# Sheet1.net
KiCad netlist of a schematic drawn in Altium Designer
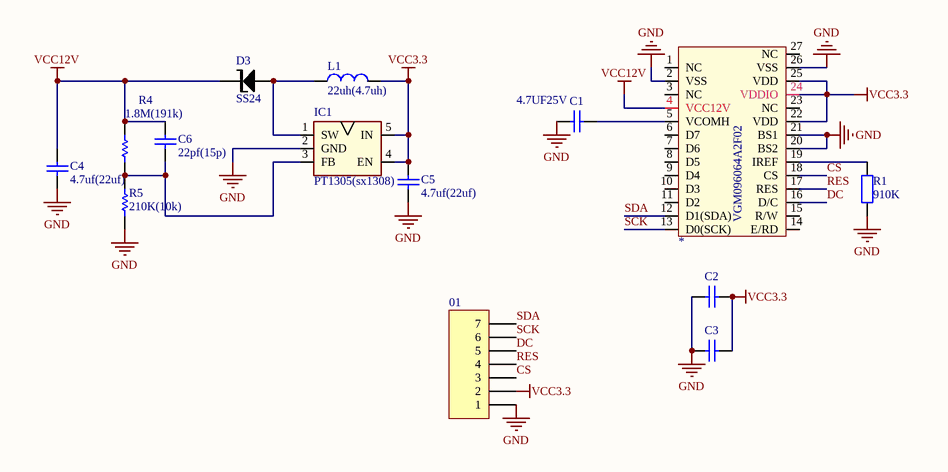
[diagram p0: Sheet1.SchDoc]

(export (version "E")
  (design (tool "Eeschema 10.0.6"))
  (components
    (comp (ref "*")
      (value "VGM096064A2F02")
      (footprint "VGM096064A2F02")
      (libsource (lib "COG-C177MVHG-03(pin23_08)") (part "VGM096064A2F02"))
    )
    (comp (ref "01")
      (value "Header 7")
      (footprint "HDR1X7")
      (description "Header, 7-Pin")
      (fields (field (name "PUBLISHER") "Altium Limited"))
      (libsource (lib "Miscellaneous Connectors") (part "Header 7"))
    )
    (comp (ref "C1")
      (value "4.7UF25V")
      (footprint "LC-0805_C")
      (description "Capacitor")
      (fields (field (name "Comment") "Cap") (field (name "PUBLISHER") "Altium Limited"))
      (libsource (lib "Miscellaneous Devices") (part "Cap"))
    )
    (comp (ref "C2")
      (value "Cap")
      (footprint "LC-0805_C")
      (description "Capacitor")
      (fields (field (name "PUBLISHER") "Altium Limited"))
      (libsource (lib "Miscellaneous Devices") (part "Cap"))
    )
    (comp (ref "C3")
      (value "Cap")
      (footprint "LC-0805_C")
      (description "Capacitor")
      (fields (field (name "PUBLISHER") "Altium Limited"))
      (libsource (lib "Miscellaneous Devices") (part "Cap"))
    )
    (comp (ref "C4")
      (value "4.7uf(22uf)")
      (footprint "LC-0805_C")
      (description "Capacitor")
      (fields (field (name "Comment") "Cap") (field (name "PUBLISHER") "Altium Limited"))
      (libsource (lib "Miscellaneous Devices") (part "Cap"))
    )
    (comp (ref "C5")
      (value "4.7uf(22uf)")
      (footprint "LC-0805_C")
      (description "Capacitor")
      (fields (field (name "Comment") "Cap") (field (name "PUBLISHER") "Altium Limited"))
      (libsource (lib "Miscellaneous Devices") (part "Cap"))
    )
    (comp (ref "C6")
      (value "22pf(15p)")
      (footprint "LC-0805_C")
      (description "Capacitor")
      (fields (field (name "Comment") "Cap") (field (name "PUBLISHER") "Altium Limited"))
      (libsource (lib "Miscellaneous Devices") (part "Cap"))
    )
    (comp (ref "D3")
      (value "SS24")
      (footprint "LC-0805")
      (description "肖特基二极管")
      (fields (field (name "版权归属") "源创客"))
      (libsource (lib "Power_CHIP") (part "SS24"))
    )
    (comp (ref "IC1")
      (value "PT1305(sx1308)")
      (footprint "LC-SOT-23-5")
      (libsource (lib "Power_CHIP") (part "PT1305"))
    )
    (comp (ref "L1")
      (value "22uh(4.7uh)")
      (footprint "CD31")
      (libsource (lib "Power_CHIP") (part "Inductor"))
    )
    (comp (ref "R1")
      (value "910K")
      (footprint "LC-0805_R")
      (description "Resistor")
      (fields (field (name "Comment") "Res2") (field (name "PUBLISHER") "Altium Limited"))
      (libsource (lib "Miscellaneous Devices") (part "Res2"))
    )
    (comp (ref "R4")
      (value "1.8M(191k)")
      (footprint "LC-0805_R")
      (description "Resistor")
      (fields (field (name "Comment") "Res1") (field (name "PUBLISHER") "Altium Limited"))
      (libsource (lib "Miscellaneous Devices") (part "Res1"))
    )
    (comp (ref "R5")
      (value "210K(10k)")
      (footprint "LC-0805_R")
      (description "Resistor")
      (fields (field (name "Comment") "Res1") (field (name "PUBLISHER") "Altium Limited"))
      (libsource (lib "Miscellaneous Devices") (part "Res1"))
    )
  )
  (nets
    (net (code "1") (name "/CS") (class "Default")
      (node (ref "*") (pin "18") (pinfunction "CS_18") (pintype "passive"))
      (node (ref "01") (pin "3") (pinfunction "3_3") (pintype "passive"))
    )
    (net (code "2") (name "/DC") (class "Default")
      (node (ref "*") (pin "16") (pinfunction "D/C_16") (pintype "passive"))
      (node (ref "01") (pin "5") (pinfunction "5_5") (pintype "passive"))
    )
    (net (code "3") (name "/RES") (class "Default")
      (node (ref "*") (pin "17") (pinfunction "RES_17") (pintype "passive"))
      (node (ref "01") (pin "4") (pinfunction "4_4") (pintype "passive"))
    )
    (net (code "4") (name "/SCK") (class "Default")
      (node (ref "*") (pin "13") (pinfunction "D0(SCK)_13") (pintype "passive"))
      (node (ref "01") (pin "6") (pinfunction "6_6") (pintype "passive"))
    )
    (net (code "5") (name "/SDA") (class "Default")
      (node (ref "*") (pin "12") (pinfunction "D1(SDA)_12") (pintype "passive"))
      (node (ref "01") (pin "7") (pinfunction "7_7") (pintype "passive"))
    )
    (net (code "6") (name "GND") (class "Default")
      (node (ref "*") (pin "2") (pinfunction "VSS_2") (pintype "passive"))
      (node (ref "*") (pin "20") (pinfunction "BS2_20") (pintype "passive"))
      (node (ref "*") (pin "21") (pinfunction "BS1_21") (pintype "passive"))
      (node (ref "*") (pin "26") (pinfunction "VSS_26") (pintype "passive"))
      (node (ref "01") (pin "1") (pinfunction "1_1") (pintype "passive"))
      (node (ref "C1") (pin "1") (pinfunction "1_1") (pintype "passive"))
      (node (ref "C2") (pin "1") (pinfunction "1_1") (pintype "passive"))
      (node (ref "C3") (pin "1") (pinfunction "1_1") (pintype "passive"))
      (node (ref "C4") (pin "1") (pinfunction "1_1") (pintype "passive"))
      (node (ref "C5") (pin "1") (pinfunction "1_1") (pintype "passive"))
      (node (ref "IC1") (pin "2") (pinfunction "GND_2") (pintype "passive"))
      (node (ref "R1") (pin "1") (pinfunction "1_1") (pintype "passive"))
      (node (ref "R5") (pin "1") (pinfunction "1_1") (pintype "passive"))
    )
    (net (code "7") (name "Net-(*-IREF)") (class "Default")
      (node (ref "*") (pin "19") (pinfunction "IREF_19") (pintype "passive"))
      (node (ref "R1") (pin "2") (pinfunction "2_2") (pintype "passive"))
    )
    (net (code "8") (name "Net-(*-VCOMH)") (class "Default")
      (node (ref "*") (pin "5") (pinfunction "VCOMH_5") (pintype "passive"))
      (node (ref "C1") (pin "2") (pinfunction "2_2") (pintype "passive"))
    )
    (net (code "9") (name "Net-(D3-A)") (class "Default")
      (node (ref "D3") (pin "1") (pinfunction "A_1") (pintype "passive"))
      (node (ref "IC1") (pin "1") (pinfunction "SW_1") (pintype "passive"))
      (node (ref "L1") (pin "2") (pinfunction "2_2") (pintype "passive"))
    )
    (net (code "10") (name "Net-(IC1-FB)") (class "Default")
      (node (ref "C6") (pin "1") (pinfunction "1_1") (pintype "passive"))
      (node (ref "IC1") (pin "3") (pinfunction "FB_3") (pintype "passive"))
      (node (ref "R4") (pin "1") (pinfunction "1_1") (pintype "passive"))
      (node (ref "R5") (pin "2") (pinfunction "2_2") (pintype "passive"))
    )
    (net (code "11") (name "VCC3.3") (class "Default")
      (node (ref "*") (pin "22") (pinfunction "VDD_22") (pintype "passive"))
      (node (ref "*") (pin "24") (pinfunction "VDDIO_24") (pintype "passive"))
      (node (ref "*") (pin "25") (pinfunction "VDD_25") (pintype "passive"))
      (node (ref "01") (pin "2") (pinfunction "2_2") (pintype "passive"))
      (node (ref "C2") (pin "2") (pinfunction "2_2") (pintype "passive"))
      (node (ref "C3") (pin "2") (pinfunction "2_2") (pintype "passive"))
      (node (ref "C5") (pin "2") (pinfunction "2_2") (pintype "passive"))
      (node (ref "IC1") (pin "4") (pinfunction "EN_4") (pintype "passive"))
      (node (ref "IC1") (pin "5") (pinfunction "IN_5") (pintype "passive"))
      (node (ref "L1") (pin "1") (pinfunction "1_1") (pintype "passive"))
    )
    (net (code "12") (name "VCC12V") (class "Default")
      (node (ref "*") (pin "4") (pinfunction "VCC12V_4") (pintype "passive"))
      (node (ref "C4") (pin "2") (pinfunction "2_2") (pintype "passive"))
      (node (ref "C6") (pin "2") (pinfunction "2_2") (pintype "passive"))
      (node (ref "D3") (pin "2") (pinfunction "K_2") (pintype "passive"))
      (node (ref "R4") (pin "2") (pinfunction "2_2") (pintype "passive"))
    )
    (net (code "13") (name "unconnected-(*-D2-Pad11)") (class "Default")
      (node (ref "*") (pin "11") (pinfunction "D2_11") (pintype "passive"))
    )
    (net (code "14") (name "unconnected-(*-D3-Pad10)") (class "Default")
      (node (ref "*") (pin "10") (pinfunction "D3_10") (pintype "passive"))
    )
    (net (code "15") (name "unconnected-(*-D4-Pad9)") (class "Default")
      (node (ref "*") (pin "9") (pinfunction "D4_9") (pintype "passive"))
    )
    (net (code "16") (name "unconnected-(*-D5-Pad8)") (class "Default")
      (node (ref "*") (pin "8") (pinfunction "D5_8") (pintype "passive"))
    )
    (net (code "17") (name "unconnected-(*-D6-Pad7)") (class "Default")
      (node (ref "*") (pin "7") (pinfunction "D6_7") (pintype "passive"))
    )
    (net (code "18") (name "unconnected-(*-D7-Pad6)") (class "Default")
      (node (ref "*") (pin "6") (pinfunction "D7_6") (pintype "passive"))
    )
    (net (code "19") (name "unconnected-(*-E{slash}RD-Pad14)") (class "Default")
      (node (ref "*") (pin "14") (pinfunction "E/RD_14") (pintype "passive"))
    )
    (net (code "20") (name "unconnected-(*-NC-Pad1)") (class "Default")
      (node (ref "*") (pin "1") (pinfunction "NC_1") (pintype "passive"))
    )
    (net (code "21") (name "unconnected-(*-NC-Pad3)") (class "Default")
      (node (ref "*") (pin "3") (pinfunction "NC_3") (pintype "passive"))
    )
    (net (code "22") (name "unconnected-(*-NC-Pad23)") (class "Default")
      (node (ref "*") (pin "23") (pinfunction "NC_23") (pintype "passive"))
    )
    (net (code "23") (name "unconnected-(*-NC-Pad27)") (class "Default")
      (node (ref "*") (pin "27") (pinfunction "NC_27") (pintype "passive"))
    )
    (net (code "24") (name "unconnected-(*-R{slash}W-Pad15)") (class "Default")
      (node (ref "*") (pin "15") (pinfunction "R/W_15") (pintype "passive"))
    )
  )
)
